# L-D5019-01-04.net
KiCad netlist of a schematic drawn in Altium Designer
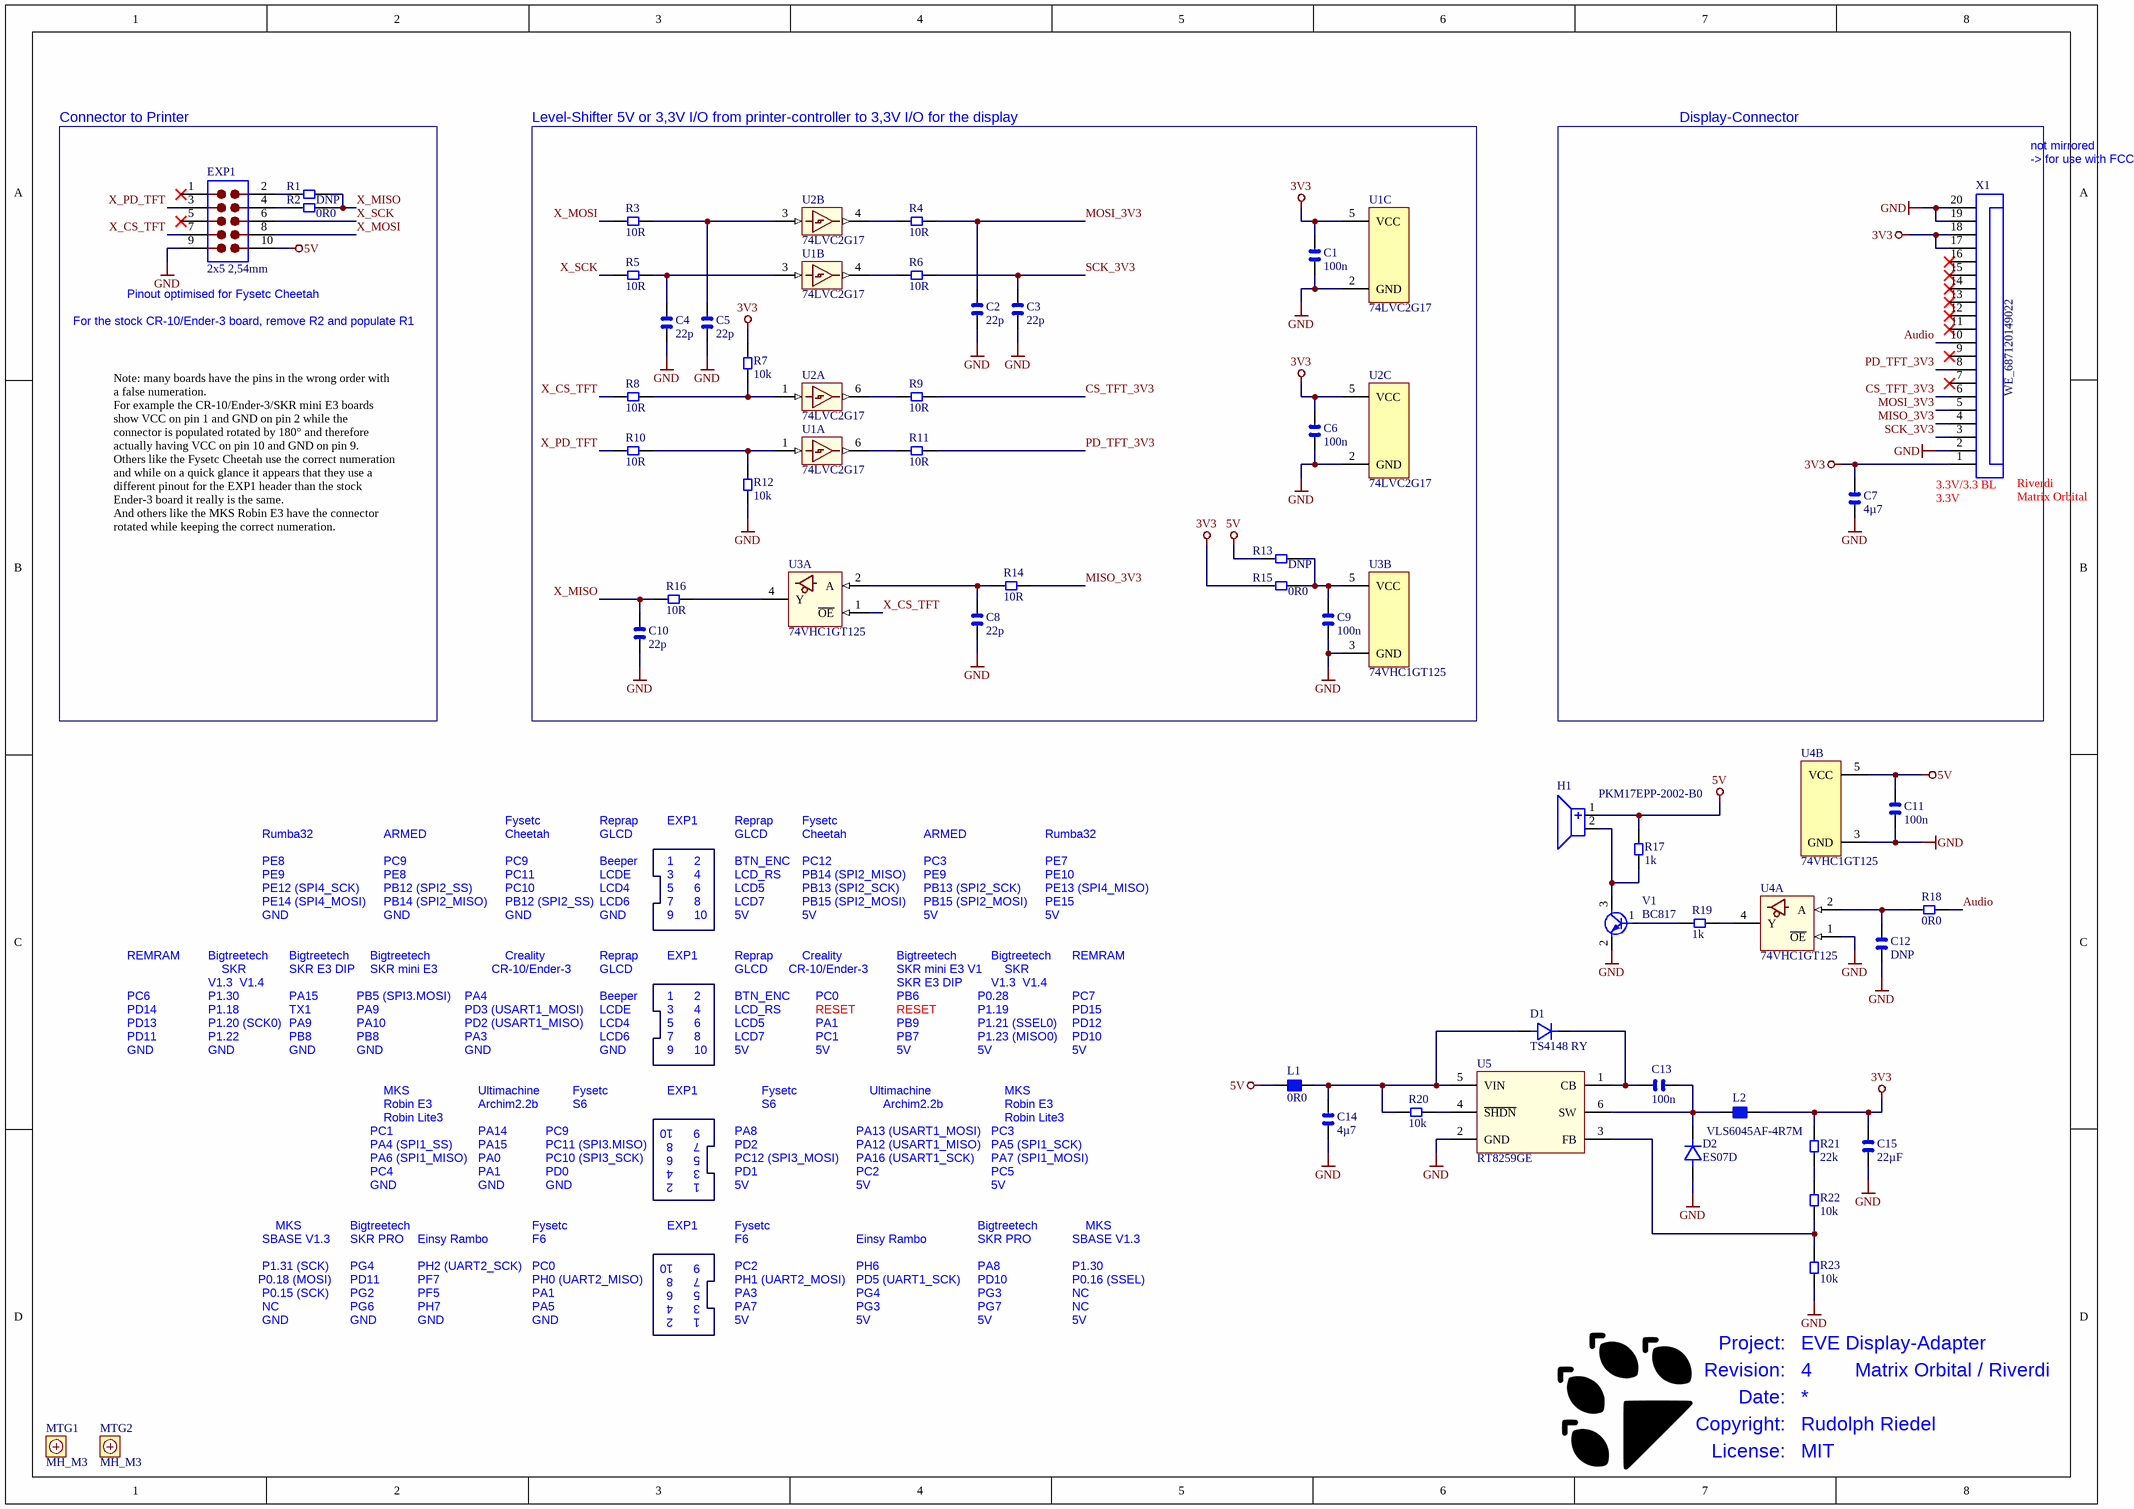
[diagram p0: L-D5019-01-04.SchDoc]

(export (version "E")
  (design (tool "Eeschema 10.0.6"))
  (components
    (comp (ref "C1")
      (value "100n")
      (footprint "CAPC2012X14L")
      (description "0805 Chip Capacitor")
      (fields (field (name "PART NUMBER") "CAPC_0805") (field (name "EDITOR") "rriedel"))
      (libsource (lib "HW-Labor_GF") (part "CAP_2_V2"))
    )
    (comp (ref "C2")
      (value "22p")
      (footprint "CAPC2012X14L")
      (description "0805 Chip Capacitor")
      (fields (field (name "PART NUMBER") "CAPC_0805") (field (name "EDITOR") "rriedel"))
      (libsource (lib "HW-Labor_GF") (part "CAP_2_V2"))
    )
    (comp (ref "C3")
      (value "22p")
      (footprint "CAPC2012X14L")
      (description "0805 Chip Capacitor")
      (fields (field (name "PART NUMBER") "CAPC_0805") (field (name "EDITOR") "rriedel"))
      (libsource (lib "HW-Labor_GF") (part "CAP_2_V2"))
    )
    (comp (ref "C4")
      (value "22p")
      (footprint "CAPC2012X14L")
      (description "0805 Chip Capacitor")
      (fields (field (name "PART NUMBER") "CAPC_0805") (field (name "EDITOR") "rriedel"))
      (libsource (lib "HW-Labor_GF") (part "CAP_2_V2"))
    )
    (comp (ref "C5")
      (value "22p")
      (footprint "CAPC2012X14L")
      (description "0805 Chip Capacitor")
      (fields (field (name "PART NUMBER") "CAPC_0805") (field (name "EDITOR") "rriedel"))
      (libsource (lib "HW-Labor_GF") (part "CAP_2_V2"))
    )
    (comp (ref "C6")
      (value "100n")
      (footprint "CAPC2012X14L")
      (description "0805 Chip Capacitor")
      (fields (field (name "PART NUMBER") "CAPC_0805") (field (name "EDITOR") "rriedel"))
      (libsource (lib "HW-Labor_GF") (part "CAP_2_V2"))
    )
    (comp (ref "C7")
      (value "4µ7")
      (footprint "CAPC2012X14L")
      (description "0805 Chip Capacitor")
      (fields (field (name "PART NUMBER") "CAPC_0805") (field (name "ERSTELLER") "rriedel"))
      (libsource (lib "HW-Labor_GF") (part "CAP_2_V2"))
    )
    (comp (ref "C8")
      (value "22p")
      (footprint "CAPC2012X14L")
      (description "0805 Chip Capacitor")
      (fields (field (name "PART NUMBER") "CAPC_0805") (field (name "EDITOR") "rriedel"))
      (libsource (lib "HW-Labor_GF") (part "CAP_2_V2"))
    )
    (comp (ref "C9")
      (value "100n")
      (footprint "CAPC2012X14L")
      (description "0805 Chip Capacitor")
      (fields (field (name "PART NUMBER") "CAPC_0805") (field (name "EDITOR") "rriedel"))
      (libsource (lib "HW-Labor_GF") (part "CAP_2_V2"))
    )
    (comp (ref "C10")
      (value "22p")
      (footprint "CAPC2012X14L")
      (description "0805 Chip Capacitor")
      (fields (field (name "PART NUMBER") "CAPC_0805") (field (name "EDITOR") "rriedel"))
      (libsource (lib "HW-Labor_GF") (part "CAP_2_V2"))
    )
    (comp (ref "C11")
      (value "100n")
      (footprint "CAPC2012X14L")
      (description "0805 Chip Capacitor")
      (fields (field (name "PART NUMBER") "CAPC_0805") (field (name "EDITOR") "rriedel"))
      (libsource (lib "HW-Labor_GF") (part "CAP_2_V2"))
    )
    (comp (ref "C12")
      (value "DNP")
      (footprint "CAPC2012X14L")
      (description "0805 Chip Capacitor")
      (fields (field (name "PART NUMBER") "CAPC_0805") (field (name "EDITOR") "rriedel"))
      (libsource (lib "HW-Labor_GF") (part "CAP_2_V2"))
    )
    (comp (ref "C13")
      (value "100n")
      (footprint "CAPC2012X14L")
      (description "0805 Chip Capacitor")
      (fields (field (name "PART NUMBER") "CAPC_0805") (field (name "EDITOR") "rriedel"))
      (libsource (lib "HW-Labor_GF") (part "CAP_2_V2"))
    )
    (comp (ref "C14")
      (value "4µ7")
      (footprint "CAPC2012X14L")
      (description "0805 Chip Capacitor")
      (fields (field (name "PART NUMBER") "CAPC_0805") (field (name "ERSTELLER") "rriedel"))
      (libsource (lib "HW-Labor_GF") (part "CAP_2_V2"))
    )
    (comp (ref "C15")
      (value "22µF")
      (footprint "CAPC3216X19N")
      (description "1206 Chip Capacitor")
      (fields (field (name "PART NUMBER") "CAPC_1206") (field (name "EDITOR") "rriedel"))
      (libsource (lib "HW-Labor_GF") (part "CAP_2_V2"))
    )
    (comp (ref "D1")
      (value "TS4148 RY")
      (footprint "DIOC2012X10N")
      (description "Small Signal Diode IF 0.3A, VR 75V, 0805")
      (fields
        (field (name "PART NUMBER") "TSC_TS4148 RY")
        (field (name "MANUFACTURER") "TSC")
        (field (name "EDITOR") "rriedel")
      )
      (libsource (lib "HW-Labor_GF") (part "Diode_A2_K1"))
    )
    (comp (ref "D2")
      (value "ES07D")
      (footprint "DIOM2818X11N")
      (description "Ultrafast Rectifier Surface Mount,  IF 0.5A, VR 100V, DO-219AB, AEC-Q101")
      (fields (field (name "MANUFACTURER") "Vishay") (field (name "EDITOR") "rriedel"))
      (libsource (lib "HW-Labor_GF") (part "Diode_A2_K1"))
    )
    (comp (ref "EXP1")
      (value "2x5 2,54mm")
      (footprint "PINH_2x5_2_54mm_shroud")
      (description "Pin-Header 2,54 mm 2x5pins, shrouded")
      (fields (field (name "PART NUMBER") "PINH_2x5_2_54") (field (name "EDITOR") "rriedel"))
      (libsource (lib "HW-Labor_GF") (part "CONM_2x5_V2"))
    )
    (comp (ref "H1")
      (value "PKM17EPP-2002-B0")
      (footprint "Speaker_17mm")
      (description "Speaker, Piezo, THT, dia 17mm,  height 8.6 mm")
      (fields
        (field (name "MANUFACTURER") "Murata")
        (field (name "DISTRIBUTOR_1_PART_NUMBER") "490-4688-ND")
        (field (name "EDITOR") "rriedel")
      )
      (libsource (lib "HW-Labor_GF") (part "Speaker"))
    )
    (comp (ref "L1")
      (value "0R0")
      (footprint "INDC2012X10L")
      (description "0805 Chip Inductor")
      (fields (field (name "PART NUMBER") "INDC_0805") (field (name "EDITOR") "rriedel"))
      (libsource (lib "HW-Labor_GF") (part "IND_2_V1"))
    )
    (comp (ref "L2")
      (value "VLS6045AF-4R7M")
      (footprint "PowerInductor_6x6")
      (description "4,7µH, shielded, 4,7A, 26mR")
      (fields
        (field (name "MANUFACTURER") "TDK")
        (field (name "DISTRIBUTOR_1_PART_NUMBER") "445-180835-1-ND")
        (field (name "EDITOR") "rriedel")
      )
      (libsource (lib "HW-Labor_GF") (part "IND_2_V1"))
    )
    (comp (ref "MTG1")
      (value "MH_M3")
      (footprint "HOLE_3_2MM")
      (description "Mounting-Hole for M3 screws")
      (fields (field (name "EDITOR") "rriedel"))
      (libsource (lib "HW-Labor_GF") (part "MTG_V1"))
    )
    (comp (ref "MTG2")
      (value "MH_M3")
      (footprint "HOLE_3_2MM")
      (description "Mounting-Hole for M3 screws")
      (fields (field (name "EDITOR") "rriedel"))
      (libsource (lib "HW-Labor_GF") (part "MTG_V1"))
    )
    (comp (ref "R1")
      (value "DNP")
      (footprint "RESC2012X06L")
      (description "0805 Chip Resistor")
      (fields (field (name "PART NUMBER") "RESC_0805") (field (name "EDITOR") "rriedel"))
      (libsource (lib "HW-Labor_GF") (part "RES_2_V2"))
    )
    (comp (ref "R2")
      (value "0R0")
      (footprint "RESC2012X06L")
      (description "0805 Chip Resistor")
      (fields (field (name "PART NUMBER") "RESC_0805") (field (name "EDITOR") "rriedel"))
      (libsource (lib "HW-Labor_GF") (part "RES_2_V2"))
    )
    (comp (ref "R3")
      (value "10R")
      (footprint "RESC2012X06L")
      (description "0805 Chip Resistor")
      (fields (field (name "PART NUMBER") "RESC_0805") (field (name "EDITOR") "rriedel"))
      (libsource (lib "HW-Labor_GF") (part "RES_2_V2"))
    )
    (comp (ref "R4")
      (value "10R")
      (footprint "RESC2012X06L")
      (description "0805 Chip Resistor")
      (fields (field (name "PART NUMBER") "RESC_0805") (field (name "EDITOR") "rriedel"))
      (libsource (lib "HW-Labor_GF") (part "RES_2_V2"))
    )
    (comp (ref "R5")
      (value "10R")
      (footprint "RESC2012X06L")
      (description "0805 Chip Resistor")
      (fields (field (name "PART NUMBER") "RESC_0805") (field (name "EDITOR") "rriedel"))
      (libsource (lib "HW-Labor_GF") (part "RES_2_V2"))
    )
    (comp (ref "R6")
      (value "10R")
      (footprint "RESC2012X06L")
      (description "0805 Chip Resistor")
      (fields (field (name "PART NUMBER") "RESC_0805") (field (name "EDITOR") "rriedel"))
      (libsource (lib "HW-Labor_GF") (part "RES_2_V2"))
    )
    (comp (ref "R7")
      (value "10k")
      (footprint "RESC2012X06L")
      (description "0805 Chip Resistor")
      (fields (field (name "PART NUMBER") "RESC_0805") (field (name "EDITOR") "rriedel"))
      (libsource (lib "HW-Labor_GF") (part "RES_2_V2"))
    )
    (comp (ref "R8")
      (value "10R")
      (footprint "RESC2012X06L")
      (description "0805 Chip Resistor")
      (fields (field (name "PART NUMBER") "RESC_0805") (field (name "EDITOR") "rriedel"))
      (libsource (lib "HW-Labor_GF") (part "RES_2_V2"))
    )
    (comp (ref "R9")
      (value "10R")
      (footprint "RESC2012X06L")
      (description "0805 Chip Resistor")
      (fields (field (name "PART NUMBER") "RESC_0805") (field (name "EDITOR") "rriedel"))
      (libsource (lib "HW-Labor_GF") (part "RES_2_V2"))
    )
    (comp (ref "R10")
      (value "10R")
      (footprint "RESC2012X06L")
      (description "0805 Chip Resistor")
      (fields (field (name "PART NUMBER") "RESC_0805") (field (name "EDITOR") "rriedel"))
      (libsource (lib "HW-Labor_GF") (part "RES_2_V2"))
    )
    (comp (ref "R11")
      (value "10R")
      (footprint "RESC2012X06L")
      (description "0805 Chip Resistor")
      (fields (field (name "PART NUMBER") "RESC_0805") (field (name "EDITOR") "rriedel"))
      (libsource (lib "HW-Labor_GF") (part "RES_2_V2"))
    )
    (comp (ref "R12")
      (value "10k")
      (footprint "RESC2012X06L")
      (description "0805 Chip Resistor")
      (fields (field (name "PART NUMBER") "RESC_0805") (field (name "EDITOR") "rriedel"))
      (libsource (lib "HW-Labor_GF") (part "RES_2_V2"))
    )
    (comp (ref "R13")
      (value "DNP")
      (footprint "RESC2012X06L")
      (description "0805 Chip Resistor")
      (fields (field (name "PART NUMBER") "RESC_0805") (field (name "EDITOR") "rriedel"))
      (libsource (lib "HW-Labor_GF") (part "RES_2_V2"))
    )
    (comp (ref "R14")
      (value "10R")
      (footprint "RESC2012X06L")
      (description "0805 Chip Resistor")
      (fields (field (name "PART NUMBER") "RESC_0805") (field (name "EDITOR") "rriedel"))
      (libsource (lib "HW-Labor_GF") (part "RES_2_V2"))
    )
    (comp (ref "R15")
      (value "0R0")
      (footprint "RESC2012X06L")
      (description "0805 Chip Resistor")
      (fields (field (name "PART NUMBER") "RESC_0805") (field (name "EDITOR") "rriedel"))
      (libsource (lib "HW-Labor_GF") (part "RES_2_V2"))
    )
    (comp (ref "R16")
      (value "10R")
      (footprint "RESC2012X06L")
      (description "0805 Chip Resistor")
      (fields (field (name "PART NUMBER") "RESC_0805") (field (name "EDITOR") "rriedel"))
      (libsource (lib "HW-Labor_GF") (part "RES_2_V2"))
    )
    (comp (ref "R17")
      (value "1k")
      (footprint "RESC2012X06L")
      (description "0805 Chip Resistor")
      (fields (field (name "PART NUMBER") "RESC_0805") (field (name "EDITOR") "rriedel"))
      (libsource (lib "HW-Labor_GF") (part "RES_2_V2"))
    )
    (comp (ref "R18")
      (value "0R0")
      (footprint "RESC2012X06L")
      (description "0805 Chip Resistor")
      (fields (field (name "PART NUMBER") "RESC_0805") (field (name "EDITOR") "rriedel"))
      (libsource (lib "HW-Labor_GF") (part "RES_2_V2"))
    )
    (comp (ref "R19")
      (value "1k")
      (footprint "RESC2012X06L")
      (description "0805 Chip Resistor")
      (fields (field (name "PART NUMBER") "RESC_0805") (field (name "EDITOR") "rriedel"))
      (libsource (lib "HW-Labor_GF") (part "RES_2_V2"))
    )
    (comp (ref "R20")
      (value "10k")
      (footprint "RESC2012X06L")
      (description "0805 Chip Resistor")
      (fields (field (name "PART NUMBER") "RESC_0805") (field (name "EDITOR") "rriedel"))
      (libsource (lib "HW-Labor_GF") (part "RES_2_V2"))
    )
    (comp (ref "R21")
      (value "22k")
      (footprint "RESC2012X06L")
      (description "0805 Chip Resistor")
      (fields (field (name "PART NUMBER") "RESC_0805") (field (name "EDITOR") "rriedel"))
      (libsource (lib "HW-Labor_GF") (part "RES_2_V2"))
    )
    (comp (ref "R22")
      (value "10k")
      (footprint "RESC2012X06L")
      (description "0805 Chip Resistor")
      (fields (field (name "PART NUMBER") "RESC_0805") (field (name "EDITOR") "rriedel"))
      (libsource (lib "HW-Labor_GF") (part "RES_2_V2"))
    )
    (comp (ref "R23")
      (value "10k")
      (footprint "RESC2012X06L")
      (description "0805 Chip Resistor")
      (fields (field (name "PART NUMBER") "RESC_0805") (field (name "EDITOR") "rriedel"))
      (libsource (lib "HW-Labor_GF") (part "RES_2_V2"))
    )
    (comp (ref "U1")
      (value "74LVC2G17")
      (footprint "SOT95P280X110-6N")
      (description "Dual Schmitt-Trigger Buffer with 5.5V tolerant inputs")
      (fields
        (field (name "MANUFACTURER") "TI")
        (field (name "DISTRIBUTOR_1_PART_NUMBER") "296-SN74LVC2G17DBVRCT-ND‎")
        (field (name "EDITOR") "rriedel")
      )
      (libsource (lib "HW-Labor_GF") (part "74LVC2G17"))
    )
    (comp (ref "U2")
      (value "74LVC2G17")
      (footprint "SOT95P280X110-6N")
      (description "Dual Schmitt-Trigger Buffer with 5.5V tolerant inputs")
      (fields
        (field (name "MANUFACTURER") "TI")
        (field (name "DISTRIBUTOR_1_PART_NUMBER") "296-SN74LVC2G17DBVRCT-ND‎")
        (field (name "EDITOR") "rriedel")
      )
      (libsource (lib "HW-Labor_GF") (part "74LVC2G17"))
    )
    (comp (ref "U3")
      (value "74VHC1GT125")
      (footprint "SOT95P280X110-5N")
      (description "1x Buffer with OE; 3-state,Level Shifter 3,3V to 5V and 5V to 3.3V")
      (fields
        (field (name "MANUFACTURER") "ON Semiconductor")
        (field (name "DISTRIBUTOR_1_PART_NUMBER") "1703291")
        (field (name "EDITOR") "rriedel")
      )
      (libsource (lib "") (part "74LVC1G125G_1"))
    )
    (comp (ref "U4")
      (value "74VHC1GT125")
      (footprint "SOT95P280X110-5N")
      (description "1x Buffer with OE; 3-state,Level Shifter 3,3V to 5V and 5V to 3.3V")
      (fields
        (field (name "MANUFACTURER") "ON Semiconductor")
        (field (name "DISTRIBUTOR_1_PART_NUMBER") "1703291")
        (field (name "EDITOR") "rriedel")
      )
      (libsource (lib "HW-Labor_GF") (part "74LVC1G125G"))
    )
    (comp (ref "U5")
      (value "RT8259GE")
      (footprint "SOT95P280X110-6N")
      (description "Step-Down DC/DC Regulator, 24V, 1.2A, 1,4MHz")
      (fields
        (field (name "MANUFACTURER") "Richtek")
        (field (name "DISTRIBUTOR_1_PART_NUMBER") "1028-1497-1-ND")
        (field (name "EDITOR") "rriedel")
      )
      (libsource (lib "HW-Labor_GF") (part "StepDown_SOT23-6"))
    )
    (comp (ref "V1")
      (value "BC817")
      (footprint "SOT95P280X110-3N")
      (description "NPN Transistor SOT23, 1=B, 2=C, 3=E")
      (fields (field (name "EDITOR") "rriedel"))
      (libsource (lib "HW-Labor_GF") (part "NPN_B1_C2_E3"))
    )
    (comp (ref "X1")
      (value "WE_687120149022")
      (footprint "WE_687120149022")
      (description "20pin WR-FPC 0.50 mm SMT ZIF Horizontal - Bottom Contact")
      (fields
        (field (name "MANUFACTURER") "Wuerth")
        (field (name "DISTRIBUTOR_1_PART_NUMBER") "732-6002-1-ND")
        (field (name "EDITOR") "rriedel")
      )
      (libsource (lib "HW-Labor_GF") (part "FPC_20"))
    )
  )
  (nets
    (net (code "1") (name "/Audio") (class "Default")
      (node (ref "R18") (pin "2") (pinfunction "2_2") (pintype "passive"))
      (node (ref "X1") (pin "10") (pinfunction "10_10") (pintype "passive"))
    )
    (net (code "2") (name "/CS_TFT_3V3") (class "Default")
      (node (ref "R9") (pin "2") (pinfunction "2_2") (pintype "passive"))
      (node (ref "X1") (pin "6") (pinfunction "6_6") (pintype "passive"))
    )
    (net (code "3") (name "/MISO_3V3") (class "Default")
      (node (ref "R14") (pin "2") (pinfunction "2_2") (pintype "passive"))
      (node (ref "X1") (pin "4") (pinfunction "4_4") (pintype "passive"))
    )
    (net (code "4") (name "/MOSI_3V3") (class "Default")
      (node (ref "C2") (pin "2") (pinfunction "2_2") (pintype "passive"))
      (node (ref "R4") (pin "2") (pinfunction "2_2") (pintype "passive"))
      (node (ref "X1") (pin "5") (pinfunction "5_5") (pintype "passive"))
    )
    (net (code "5") (name "/PD_TFT_3V3") (class "Default")
      (node (ref "R11") (pin "2") (pinfunction "2_2") (pintype "passive"))
      (node (ref "X1") (pin "8") (pinfunction "8_8") (pintype "passive"))
    )
    (net (code "6") (name "/SCK_3V3") (class "Default")
      (node (ref "C3") (pin "2") (pinfunction "2_2") (pintype "passive"))
      (node (ref "R6") (pin "2") (pinfunction "2_2") (pintype "passive"))
      (node (ref "X1") (pin "3") (pinfunction "3_3") (pintype "passive"))
    )
    (net (code "7") (name "/X_CS_TFT") (class "Default")
      (node (ref "EXP1") (pin "7") (pinfunction "7_7") (pintype "passive"))
      (node (ref "R8") (pin "1") (pinfunction "1_1") (pintype "passive"))
      (node (ref "U3") (pin "1") (pinfunction "~{OE}_1") (pintype "input"))
    )
    (net (code "8") (name "/X_MISO") (class "Default")
      (node (ref "C10") (pin "2") (pinfunction "2_2") (pintype "passive"))
      (node (ref "R1") (pin "2") (pinfunction "2_2") (pintype "passive"))
      (node (ref "R16") (pin "1") (pinfunction "1_1") (pintype "passive"))
      (node (ref "R2") (pin "2") (pinfunction "2_2") (pintype "passive"))
    )
    (net (code "9") (name "/X_MOSI") (class "Default")
      (node (ref "EXP1") (pin "8") (pinfunction "8_8") (pintype "passive"))
      (node (ref "R3") (pin "1") (pinfunction "1_1") (pintype "passive"))
    )
    (net (code "10") (name "/X_PD_TFT") (class "Default")
      (node (ref "EXP1") (pin "3") (pinfunction "3_3") (pintype "passive"))
      (node (ref "R10") (pin "1") (pinfunction "1_1") (pintype "passive"))
    )
    (net (code "11") (name "/X_SCK") (class "Default")
      (node (ref "EXP1") (pin "6") (pinfunction "6_6") (pintype "passive"))
      (node (ref "R5") (pin "1") (pinfunction "1_1") (pintype "passive"))
    )
    (net (code "12") (name "3V3") (class "Default")
      (node (ref "C1") (pin "2") (pinfunction "2_2") (pintype "passive"))
      (node (ref "C15") (pin "2") (pinfunction "2_2") (pintype "passive"))
      (node (ref "C6") (pin "2") (pinfunction "2_2") (pintype "passive"))
      (node (ref "C7") (pin "2") (pinfunction "2_2") (pintype "passive"))
      (node (ref "L2") (pin "2") (pinfunction "2_2") (pintype "passive"))
      (node (ref "R15") (pin "1") (pinfunction "1_1") (pintype "passive"))
      (node (ref "R21") (pin "2") (pinfunction "2_2") (pintype "passive"))
      (node (ref "R7") (pin "2") (pinfunction "2_2") (pintype "passive"))
      (node (ref "U1") (pin "5") (pinfunction "VCC_5") (pintype "power_in"))
      (node (ref "U2") (pin "5") (pinfunction "VCC_5") (pintype "power_in"))
      (node (ref "X1") (pin "1") (pinfunction "1_1") (pintype "passive"))
      (node (ref "X1") (pin "17") (pinfunction "17_17") (pintype "passive"))
      (node (ref "X1") (pin "18") (pinfunction "18_18") (pintype "passive"))
    )
    (net (code "13") (name "5V") (class "Default")
      (node (ref "C11") (pin "2") (pinfunction "2_2") (pintype "passive"))
      (node (ref "EXP1") (pin "10") (pinfunction "10_10") (pintype "passive"))
      (node (ref "H1") (pin "1") (pinfunction "1_1") (pintype "passive"))
      (node (ref "L1") (pin "1") (pinfunction "1_1") (pintype "passive"))
      (node (ref "R13") (pin "1") (pinfunction "1_1") (pintype "passive"))
      (node (ref "R17") (pin "2") (pinfunction "2_2") (pintype "passive"))
      (node (ref "U4") (pin "5") (pinfunction "VCC_5") (pintype "passive"))
    )
    (net (code "14") (name "GND") (class "Default")
      (node (ref "C1") (pin "1") (pinfunction "1_1") (pintype "passive"))
      (node (ref "C10") (pin "1") (pinfunction "1_1") (pintype "passive"))
      (node (ref "C11") (pin "1") (pinfunction "1_1") (pintype "passive"))
      (node (ref "C12") (pin "1") (pinfunction "1_1") (pintype "passive"))
      (node (ref "C14") (pin "1") (pinfunction "1_1") (pintype "passive"))
      (node (ref "C15") (pin "1") (pinfunction "1_1") (pintype "passive"))
      (node (ref "C2") (pin "1") (pinfunction "1_1") (pintype "passive"))
      (node (ref "C3") (pin "1") (pinfunction "1_1") (pintype "passive"))
      (node (ref "C4") (pin "1") (pinfunction "1_1") (pintype "passive"))
      (node (ref "C5") (pin "1") (pinfunction "1_1") (pintype "passive"))
      (node (ref "C6") (pin "1") (pinfunction "1_1") (pintype "passive"))
      (node (ref "C7") (pin "1") (pinfunction "1_1") (pintype "passive"))
      (node (ref "C8") (pin "1") (pinfunction "1_1") (pintype "passive"))
      (node (ref "C9") (pin "1") (pinfunction "1_1") (pintype "passive"))
      (node (ref "D2") (pin "2") (pinfunction "2_2") (pintype "passive"))
      (node (ref "EXP1") (pin "9") (pinfunction "9_9") (pintype "passive"))
      (node (ref "R12") (pin "1") (pinfunction "1_1") (pintype "passive"))
      (node (ref "R23") (pin "1") (pinfunction "1_1") (pintype "passive"))
      (node (ref "U1") (pin "2") (pinfunction "GND_2") (pintype "power_in"))
      (node (ref "U2") (pin "2") (pinfunction "GND_2") (pintype "power_in"))
      (node (ref "U3") (pin "3") (pinfunction "GND_3") (pintype "passive"))
      (node (ref "U4") (pin "1") (pinfunction "~{OE}_1") (pintype "input"))
      (node (ref "U4") (pin "3") (pinfunction "GND_3") (pintype "passive"))
      (node (ref "U5") (pin "2") (pinfunction "GND_2") (pintype "power_in"))
      (node (ref "V1") (pin "2") (pinfunction "2_2") (pintype "passive"))
      (node (ref "X1") (pin "19") (pinfunction "19_19") (pintype "passive"))
      (node (ref "X1") (pin "2") (pinfunction "2_2") (pintype "passive"))
      (node (ref "X1") (pin "20") (pinfunction "20_20") (pintype "passive"))
    )
    (net (code "15") (name "Net-(EXP1-Pad2)") (class "Default")
      (node (ref "EXP1") (pin "2") (pinfunction "2_2") (pintype "passive"))
      (node (ref "R1") (pin "1") (pinfunction "1_1") (pintype "passive"))
    )
    (net (code "16") (name "Net-(EXP1-Pad4)") (class "Default")
      (node (ref "EXP1") (pin "4") (pinfunction "4_4") (pintype "passive"))
      (node (ref "R2") (pin "1") (pinfunction "1_1") (pintype "passive"))
    )
    (net (code "17") (name "Net-(H1-Pad2)") (class "Default")
      (node (ref "H1") (pin "2") (pinfunction "2_2") (pintype "passive"))
      (node (ref "R17") (pin "1") (pinfunction "1_1") (pintype "passive"))
      (node (ref "V1") (pin "3") (pinfunction "3_3") (pintype "passive"))
    )
    (net (code "18") (name "Net-(R19-Pad2)") (class "Default")
      (node (ref "R19") (pin "2") (pinfunction "2_2") (pintype "passive"))
      (node (ref "V1") (pin "1") (pinfunction "1_1") (pintype "passive"))
    )
    (net (code "19") (name "Net-(R21-Pad1)") (class "Default")
      (node (ref "R21") (pin "1") (pinfunction "1_1") (pintype "passive"))
      (node (ref "R22") (pin "2") (pinfunction "2_2") (pintype "passive"))
    )
    (net (code "20") (name "Net-(U1A-1A)") (class "Default")
      (node (ref "R10") (pin "2") (pinfunction "2_2") (pintype "passive"))
      (node (ref "R12") (pin "2") (pinfunction "2_2") (pintype "passive"))
      (node (ref "U1") (pin "1") (pinfunction "1A_1") (pintype "input"))
    )
    (net (code "21") (name "Net-(U1A-1Y)") (class "Default")
      (node (ref "R11") (pin "1") (pinfunction "1_1") (pintype "passive"))
      (node (ref "U1") (pin "6") (pinfunction "1Y_6") (pintype "output"))
    )
    (net (code "22") (name "Net-(U1B-2A)") (class "Default")
      (node (ref "C4") (pin "2") (pinfunction "2_2") (pintype "passive"))
      (node (ref "R5") (pin "2") (pinfunction "2_2") (pintype "passive"))
      (node (ref "U1") (pin "3") (pinfunction "2A_3") (pintype "input"))
    )
    (net (code "23") (name "Net-(U1B-2Y)") (class "Default")
      (node (ref "R6") (pin "1") (pinfunction "1_1") (pintype "passive"))
      (node (ref "U1") (pin "4") (pinfunction "2Y_4") (pintype "output"))
    )
    (net (code "24") (name "Net-(U2A-1A)") (class "Default")
      (node (ref "R7") (pin "1") (pinfunction "1_1") (pintype "passive"))
      (node (ref "R8") (pin "2") (pinfunction "2_2") (pintype "passive"))
      (node (ref "U2") (pin "1") (pinfunction "1A_1") (pintype "input"))
    )
    (net (code "25") (name "Net-(U2A-1Y)") (class "Default")
      (node (ref "R9") (pin "1") (pinfunction "1_1") (pintype "passive"))
      (node (ref "U2") (pin "6") (pinfunction "1Y_6") (pintype "output"))
    )
    (net (code "26") (name "Net-(U2B-2A)") (class "Default")
      (node (ref "C5") (pin "2") (pinfunction "2_2") (pintype "passive"))
      (node (ref "R3") (pin "2") (pinfunction "2_2") (pintype "passive"))
      (node (ref "U2") (pin "3") (pinfunction "2A_3") (pintype "input"))
    )
    (net (code "27") (name "Net-(U2B-2Y)") (class "Default")
      (node (ref "R4") (pin "1") (pinfunction "1_1") (pintype "passive"))
      (node (ref "U2") (pin "4") (pinfunction "2Y_4") (pintype "output"))
    )
    (net (code "28") (name "Net-(U3A-A)") (class "Default")
      (node (ref "C8") (pin "2") (pinfunction "2_2") (pintype "passive"))
      (node (ref "R14") (pin "1") (pinfunction "1_1") (pintype "passive"))
      (node (ref "U3") (pin "2") (pinfunction "A_2") (pintype "input"))
    )
    (net (code "29") (name "Net-(U3A-Y)") (class "Default")
      (node (ref "R16") (pin "2") (pinfunction "2_2") (pintype "passive"))
      (node (ref "U3") (pin "4") (pinfunction "Y_4") (pintype "tri_state"))
    )
    (net (code "30") (name "Net-(U3B-VCC)") (class "Default")
      (node (ref "C9") (pin "2") (pinfunction "2_2") (pintype "passive"))
      (node (ref "R13") (pin "2") (pinfunction "2_2") (pintype "passive"))
      (node (ref "R15") (pin "2") (pinfunction "2_2") (pintype "passive"))
      (node (ref "U3") (pin "5") (pinfunction "VCC_5") (pintype "passive"))
    )
    (net (code "31") (name "Net-(U4A-A)") (class "Default")
      (node (ref "C12") (pin "2") (pinfunction "2_2") (pintype "passive"))
      (node (ref "R18") (pin "1") (pinfunction "1_1") (pintype "passive"))
      (node (ref "U4") (pin "2") (pinfunction "A_2") (pintype "input"))
    )
    (net (code "32") (name "Net-(U4A-Y)") (class "Default")
      (node (ref "R19") (pin "1") (pinfunction "1_1") (pintype "passive"))
      (node (ref "U4") (pin "4") (pinfunction "Y_4") (pintype "tri_state"))
    )
    (net (code "33") (name "Net-(U5-CB)") (class "Default")
      (node (ref "C13") (pin "1") (pinfunction "1_1") (pintype "passive"))
      (node (ref "D1") (pin "1") (pinfunction "1_1") (pintype "passive"))
      (node (ref "U5") (pin "1") (pinfunction "CB_1") (pintype "passive"))
    )
    (net (code "34") (name "Net-(U5-FB)") (class "Default")
      (node (ref "R22") (pin "1") (pinfunction "1_1") (pintype "passive"))
      (node (ref "R23") (pin "2") (pinfunction "2_2") (pintype "passive"))
      (node (ref "U5") (pin "3") (pinfunction "FB_3") (pintype "passive"))
    )
    (net (code "35") (name "Net-(U5-SW)") (class "Default")
      (node (ref "C13") (pin "2") (pinfunction "2_2") (pintype "passive"))
      (node (ref "D2") (pin "1") (pinfunction "1_1") (pintype "passive"))
      (node (ref "L2") (pin "1") (pinfunction "1_1") (pintype "passive"))
      (node (ref "U5") (pin "6") (pinfunction "SW_6") (pintype "passive"))
    )
    (net (code "36") (name "Net-(U5-VIN)") (class "Default")
      (node (ref "C14") (pin "2") (pinfunction "2_2") (pintype "passive"))
      (node (ref "D1") (pin "2") (pinfunction "2_2") (pintype "passive"))
      (node (ref "L1") (pin "2") (pinfunction "2_2") (pintype "passive"))
      (node (ref "R20") (pin "1") (pinfunction "1_1") (pintype "passive"))
      (node (ref "U5") (pin "5") (pinfunction "VIN_5") (pintype "power_in"))
    )
    (net (code "37") (name "Net-(U5-~{SHDN})") (class "Default")
      (node (ref "R20") (pin "2") (pinfunction "2_2") (pintype "passive"))
      (node (ref "U5") (pin "4") (pinfunction "~{SHDN}_4") (pintype "passive"))
    )
    (net (code "38") (name "unconnected-(EXP1-Pad1)") (class "Default")
      (node (ref "EXP1") (pin "1") (pinfunction "1_1") (pintype "passive+no_connect"))
    )
    (net (code "39") (name "unconnected-(EXP1-Pad5)") (class "Default")
      (node (ref "EXP1") (pin "5") (pinfunction "5_5") (pintype "passive+no_connect"))
    )
    (net (code "40") (name "unconnected-(X1-Pad7)") (class "Default")
      (node (ref "X1") (pin "7") (pinfunction "7_7") (pintype "passive+no_connect"))
    )
    (net (code "41") (name "unconnected-(X1-Pad9)") (class "Default")
      (node (ref "X1") (pin "9") (pinfunction "9_9") (pintype "passive+no_connect"))
    )
    (net (code "42") (name "unconnected-(X1-Pad11)") (class "Default")
      (node (ref "X1") (pin "11") (pinfunction "11_11") (pintype "passive+no_connect"))
    )
    (net (code "43") (name "unconnected-(X1-Pad12)") (class "Default")
      (node (ref "X1") (pin "12") (pinfunction "12_12") (pintype "passive+no_connect"))
    )
    (net (code "44") (name "unconnected-(X1-Pad13)") (class "Default")
      (node (ref "X1") (pin "13") (pinfunction "13_13") (pintype "passive+no_connect"))
    )
    (net (code "45") (name "unconnected-(X1-Pad14)") (class "Default")
      (node (ref "X1") (pin "14") (pinfunction "14_14") (pintype "passive+no_connect"))
    )
    (net (code "46") (name "unconnected-(X1-Pad15)") (class "Default")
      (node (ref "X1") (pin "15") (pinfunction "15_15") (pintype "passive+no_connect"))
    )
    (net (code "47") (name "unconnected-(X1-Pad16)") (class "Default")
      (node (ref "X1") (pin "16") (pinfunction "16_16") (pintype "passive+no_connect"))
    )
  )
)
